# PIRot-schema.net
KiCad netlist of a schematic drawn in EAGLE
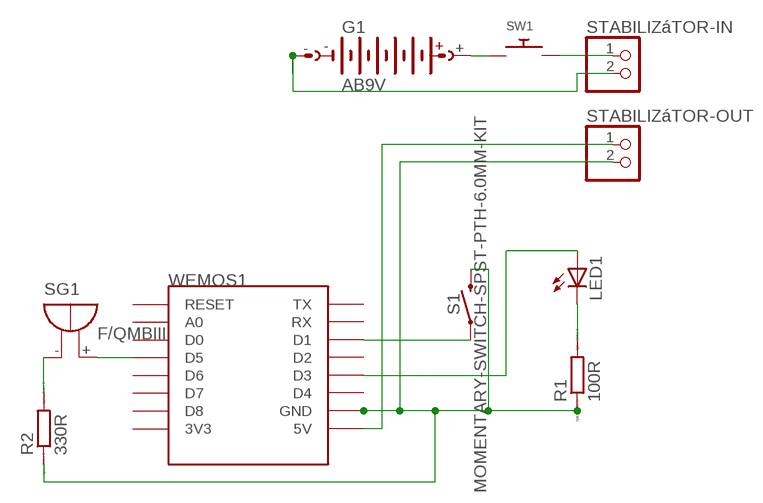
[diagram p0: schematic, sheet 1]

(export (version "E")
  (design (tool "Eeschema 10.0.6"))
  (components
    (comp (ref "G1")
      (value "AB9V")
      (footprint "eagle-import:AB9V")
      (libsource (lib "eagle-import") (part "AB9V"))
    )
    (comp (ref "LED1")
      (value "LED3MM")
      (footprint "eagle-import:LED3MM")
      (libsource (lib "eagle-import") (part "LED3MM"))
    )
    (comp (ref "R1")
      (value "100R")
      (footprint "eagle-import:0207_10")
      (libsource (lib "eagle-import") (part "R0207/10"))
    )
    (comp (ref "R2")
      (value "330R")
      (footprint "eagle-import:0207_10")
      (libsource (lib "eagle-import") (part "R0207/10"))
    )
    (comp (ref "S1")
      (value "MOMENTARY-SWITCH-SPST-PTH-6.0MM-KIT")
      (footprint "eagle-import:TACTILE_SWITCH_PTH_6.0MM_KIT")
      (libsource (lib "eagle-import") (part "MOMENTARY-SWITCH-SPST-PTH-6.0MM-KIT"))
    )
    (comp (ref "SG1")
      (value "F/QMBIII")
      (footprint "eagle-import:F_QMBIII")
      (libsource (lib "eagle-import") (part "F/QMBIII"))
    )
    (comp (ref "STABILIZáTOR-IN")
      (value "PINHD-1X2")
      (footprint "eagle-import:1X02")
      (libsource (lib "eagle-import") (part "PINHD-1X2"))
    )
    (comp (ref "STABILIZáTOR-OUT")
      (value "PINHD-1X2")
      (footprint "eagle-import:1X02")
      (libsource (lib "eagle-import") (part "PINHD-1X2"))
    )
    (comp (ref "SW1")
      (value "SWITCH_PUSHBUTTONEVQ-PE")
      (footprint "eagle-import:TACT_PANA-EVQ")
      (libsource (lib "eagle-import") (part "SWITCH_PUSHBUTTONEVQ-PE"))
    )
    (comp (ref "WEMOS1")
      (value "WEMOS-D1-MINI")
      (footprint "eagle-import:WEMOS-D1-MINI")
      (libsource (lib "eagle-import") (part "WEMOS-D1-MINI"))
    )
  )
  (nets
    (net (code "1") (name "Net-(G1-Pad+)") (class "Default")
      (node (ref "G1") (pin "+") (pinfunction "+_+") (pintype "passive"))
      (node (ref "SW1") (pin "P$1") (pinfunction "P$1_P$1") (pintype "passive"))
    )
    (net (code "2") (name "Net-(G1-Pad-)") (class "Default")
      (node (ref "G1") (pin "-") (pinfunction "-_-") (pintype "passive"))
      (node (ref "STABILIZáTOR-IN") (pin "2") (pinfunction "2_2") (pintype "passive"))
    )
    (net (code "3") (name "Net-(LED1-C)") (class "Default")
      (node (ref "LED1") (pin "K") (pinfunction "C_K") (pintype "passive"))
      (node (ref "R1") (pin "2") (pinfunction "2_2") (pintype "passive"))
    )
    (net (code "4") (name "Net-(LED1-PadA)") (class "Default")
      (node (ref "LED1") (pin "A") (pinfunction "A_A") (pintype "passive"))
      (node (ref "WEMOS1") (pin "D3") (pinfunction "D3_D3") (pintype "bidirectional"))
    )
    (net (code "5") (name "Net-(S1-2)") (class "Default")
      (node (ref "R1") (pin "1") (pinfunction "1_1") (pintype "passive"))
      (node (ref "R2") (pin "1") (pinfunction "1_1") (pintype "passive"))
      (node (ref "S1") (pin "3") (pinfunction "2_3") (pintype "passive"))
      (node (ref "STABILIZáTOR-OUT") (pin "2") (pinfunction "2_2") (pintype "passive"))
      (node (ref "WEMOS1") (pin "GND") (pinfunction "GND_GND") (pintype "bidirectional"))
    )
    (net (code "6") (name "Net-(S1-Pad1)") (class "Default")
      (node (ref "S1") (pin "1") (pinfunction "1_1") (pintype "passive"))
      (node (ref "WEMOS1") (pin "D1") (pinfunction "D1_D1") (pintype "bidirectional"))
    )
    (net (code "7") (name "Net-(SG1-+)") (class "Default")
      (node (ref "R2") (pin "2") (pinfunction "2_2") (pintype "passive"))
      (node (ref "SG1") (pin "-") (pinfunction "+_-") (pintype "passive"))
    )
    (net (code "8") (name "Net-(SG1--)") (class "Default")
      (node (ref "SG1") (pin "+") (pinfunction "-_+") (pintype "passive"))
      (node (ref "WEMOS1") (pin "D5") (pinfunction "D5_D5") (pintype "bidirectional"))
    )
    (net (code "9") (name "Net-(STABILIZáTOR-IN-Pad1)") (class "Default")
      (node (ref "STABILIZáTOR-IN") (pin "1") (pinfunction "1_1") (pintype "passive"))
      (node (ref "SW1") (pin "P$2") (pinfunction "P$2_P$2") (pintype "passive"))
    )
    (net (code "10") (name "Net-(STABILIZáTOR-OUT-Pad1)") (class "Default")
      (node (ref "STABILIZáTOR-OUT") (pin "1") (pinfunction "1_1") (pintype "passive"))
      (node (ref "WEMOS1") (pin "5V") (pinfunction "5V_5V") (pintype "bidirectional"))
    )
    (net (code "11") (name "unconnected-(WEMOS1-Pad3V3)") (class "Default")
      (node (ref "WEMOS1") (pin "3V3") (pinfunction "3V3_3V3") (pintype "bidirectional"))
    )
    (net (code "12") (name "unconnected-(WEMOS1-PadA0)") (class "Default")
      (node (ref "WEMOS1") (pin "A0") (pinfunction "A0_A0") (pintype "bidirectional"))
    )
    (net (code "13") (name "unconnected-(WEMOS1-PadD0)") (class "Default")
      (node (ref "WEMOS1") (pin "D0") (pinfunction "D0_D0") (pintype "bidirectional"))
    )
    (net (code "14") (name "unconnected-(WEMOS1-PadD2)") (class "Default")
      (node (ref "WEMOS1") (pin "D2") (pinfunction "D2_D2") (pintype "bidirectional"))
    )
    (net (code "15") (name "unconnected-(WEMOS1-PadD4)") (class "Default")
      (node (ref "WEMOS1") (pin "D4") (pinfunction "D4_D4") (pintype "bidirectional"))
    )
    (net (code "16") (name "unconnected-(WEMOS1-PadD6)") (class "Default")
      (node (ref "WEMOS1") (pin "D6") (pinfunction "D6_D6") (pintype "bidirectional"))
    )
    (net (code "17") (name "unconnected-(WEMOS1-PadD7)") (class "Default")
      (node (ref "WEMOS1") (pin "D7") (pinfunction "D7_D7") (pintype "bidirectional"))
    )
    (net (code "18") (name "unconnected-(WEMOS1-PadD8)") (class "Default")
      (node (ref "WEMOS1") (pin "D8") (pinfunction "D8_D8") (pintype "bidirectional"))
    )
    (net (code "19") (name "unconnected-(WEMOS1-PadRESET)") (class "Default")
      (node (ref "WEMOS1") (pin "RESET") (pinfunction "RESET_RESET") (pintype "bidirectional"))
    )
    (net (code "20") (name "unconnected-(WEMOS1-PadRX)") (class "Default")
      (node (ref "WEMOS1") (pin "RX") (pinfunction "RX_RX") (pintype "bidirectional"))
    )
    (net (code "21") (name "unconnected-(WEMOS1-PadTX)") (class "Default")
      (node (ref "WEMOS1") (pin "TX") (pinfunction "TX_TX") (pintype "bidirectional"))
    )
  )
)
